# ambika-smr4x.net
KiCad netlist of a schematic drawn in EAGLE
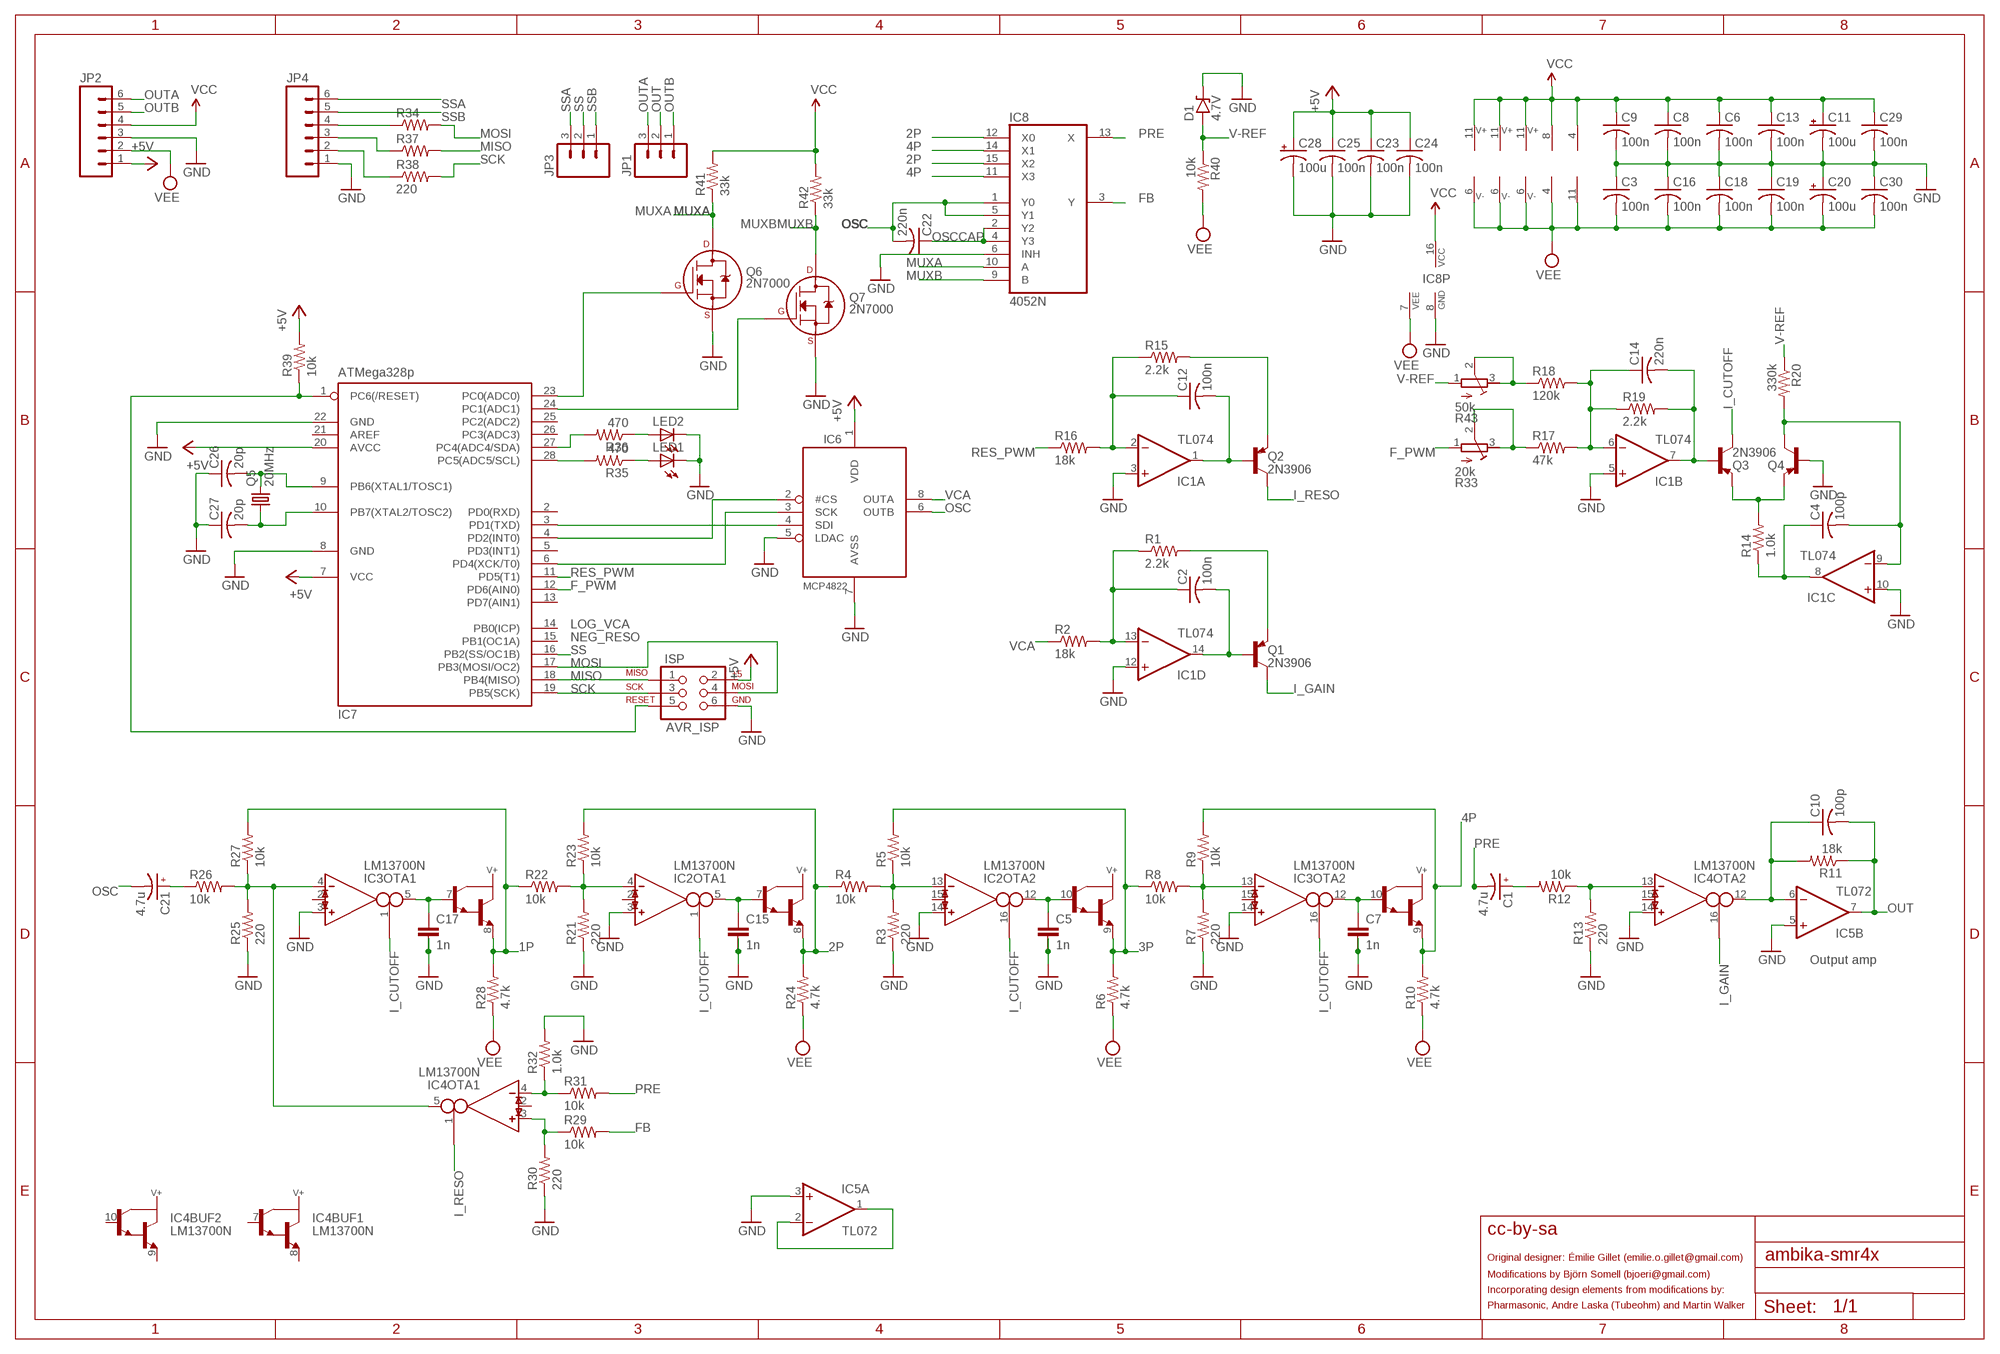
[diagram p0: schematic, sheet 1]

(export (version "E")
  (design (tool "Eeschema 10.0.6"))
  (components
    (comp (ref "C1")
      (value "4.7u")
      (footprint "eagle-import:E11-6.3")
      (libsource (lib "eagle-import") (part "CPOL-USE11-6.3"))
    )
    (comp (ref "C2")
      (value "100n")
      (footprint "eagle-import:C025-025X050")
      (libsource (lib "eagle-import") (part "C-US025-025X050"))
    )
    (comp (ref "C3")
      (value "100n")
      (footprint "eagle-import:C025-025X050")
      (libsource (lib "eagle-import") (part "C-US025-025X050"))
    )
    (comp (ref "C4")
      (value "100p")
      (footprint "eagle-import:C025-025X050")
      (libsource (lib "eagle-import") (part "C-US025-025X050"))
    )
    (comp (ref "C5")
      (value "1n")
      (footprint "eagle-import:C2.5_5-2")
      (libsource (lib "eagle-import") (part "C-2.5-5/2"))
    )
    (comp (ref "C6")
      (value "100n")
      (footprint "eagle-import:C025-025X050")
      (libsource (lib "eagle-import") (part "C-US025-025X050"))
    )
    (comp (ref "C7")
      (value "1n")
      (footprint "eagle-import:C2.5_5-2")
      (libsource (lib "eagle-import") (part "C-2.5-5/2"))
    )
    (comp (ref "C8")
      (value "100n")
      (footprint "eagle-import:C025-025X050")
      (libsource (lib "eagle-import") (part "C-US025-025X050"))
    )
    (comp (ref "C9")
      (value "100n")
      (footprint "eagle-import:C025-025X050")
      (libsource (lib "eagle-import") (part "C-US025-025X050"))
    )
    (comp (ref "C10")
      (value "100p")
      (footprint "eagle-import:C025-025X050")
      (libsource (lib "eagle-import") (part "C-US025-025X050"))
    )
    (comp (ref "C11")
      (value "100u")
      (footprint "eagle-import:E2,5-6")
      (libsource (lib "eagle-import") (part "CPOL-USE2.5-6"))
    )
    (comp (ref "C12")
      (value "100n")
      (footprint "eagle-import:C025-025X050")
      (libsource (lib "eagle-import") (part "C-US025-025X050"))
    )
    (comp (ref "C13")
      (value "100n")
      (footprint "eagle-import:C025-025X050")
      (libsource (lib "eagle-import") (part "C-US025-025X050"))
    )
    (comp (ref "C14")
      (value "220n")
      (footprint "eagle-import:C025-025X050")
      (libsource (lib "eagle-import") (part "C-US025-025X050"))
    )
    (comp (ref "C15")
      (value "1n")
      (footprint "eagle-import:C2.5_5-2")
      (libsource (lib "eagle-import") (part "C-2.5-5/2"))
    )
    (comp (ref "C16")
      (value "100n")
      (footprint "eagle-import:C025-025X050")
      (libsource (lib "eagle-import") (part "C-US025-025X050"))
    )
    (comp (ref "C17")
      (value "1n")
      (footprint "eagle-import:C2.5_5-2")
      (libsource (lib "eagle-import") (part "C-2.5-5/2"))
    )
    (comp (ref "C18")
      (value "100n")
      (footprint "eagle-import:C025-025X050")
      (libsource (lib "eagle-import") (part "C-US025-025X050"))
    )
    (comp (ref "C19")
      (value "100n")
      (footprint "eagle-import:C025-025X050")
      (libsource (lib "eagle-import") (part "C-US025-025X050"))
    )
    (comp (ref "C20")
      (value "100u")
      (footprint "eagle-import:E2,5-6")
      (libsource (lib "eagle-import") (part "CPOL-USE2.5-6"))
    )
    (comp (ref "C21")
      (value "4.7u")
      (footprint "eagle-import:E11-6.3")
      (libsource (lib "eagle-import") (part "CPOL-USE11-6.3"))
    )
    (comp (ref "C22")
      (value "220n")
      (footprint "eagle-import:C025-025X050")
      (libsource (lib "eagle-import") (part "C-US025-025X050"))
    )
    (comp (ref "C23")
      (value "100n")
      (footprint "eagle-import:C025-025X050")
      (libsource (lib "eagle-import") (part "C-US025-025X050"))
    )
    (comp (ref "C24")
      (value "100n")
      (footprint "eagle-import:C025-025X050")
      (libsource (lib "eagle-import") (part "C-US025-025X050"))
    )
    (comp (ref "C25")
      (value "100n")
      (footprint "eagle-import:C025-024X044")
      (libsource (lib "eagle-import") (part "C-US025-024X044"))
    )
    (comp (ref "C26")
      (value "20p")
      (footprint "eagle-import:C025-024X044")
      (libsource (lib "eagle-import") (part "C-US025-024X044"))
    )
    (comp (ref "C27")
      (value "20p")
      (footprint "eagle-import:C025-024X044")
      (libsource (lib "eagle-import") (part "C-US025-024X044"))
    )
    (comp (ref "C28")
      (value "100u")
      (footprint "eagle-import:E2,5-6")
      (libsource (lib "eagle-import") (part "CPOL-USE2.5-6"))
    )
    (comp (ref "C29")
      (value "100n")
      (footprint "eagle-import:C025-025X050")
      (libsource (lib "eagle-import") (part "C-US025-025X050"))
    )
    (comp (ref "C30")
      (value "100n")
      (footprint "eagle-import:C025-025X050")
      (libsource (lib "eagle-import") (part "C-US025-025X050"))
    )
    (comp (ref "D1")
      (value "4.7V")
      (footprint "eagle-import:D-5")
      (libsource (lib "eagle-import") (part "1N47XXDO35"))
    )
    (comp (ref "IC1")
      (value "TL074")
      (footprint "eagle-import:DIL14")
      (libsource (lib "eagle-import") (part "TL084P"))
    )
    (comp (ref "IC2")
      (value "LM13700N")
      (footprint "eagle-import:DIL16")
      (libsource (lib "eagle-import") (part "LM13700N"))
    )
    (comp (ref "IC3")
      (value "LM13700N")
      (footprint "eagle-import:DIL16")
      (libsource (lib "eagle-import") (part "LM13700N"))
    )
    (comp (ref "IC4")
      (value "LM13700N")
      (footprint "eagle-import:DIL16")
      (libsource (lib "eagle-import") (part "LM13700N"))
    )
    (comp (ref "IC5")
      (value "TL072")
      (footprint "eagle-import:DIL08")
      (libsource (lib "eagle-import") (part "TL072P"))
    )
    (comp (ref "IC6")
      (value "MCP4822")
      (footprint "eagle-import:DIL08")
      (libsource (lib "eagle-import") (part "MCP4822"))
    )
    (comp (ref "IC7")
      (value "ATMega328p")
      (footprint "eagle-import:DIL28-3")
      (libsource (lib "eagle-import") (part "MEGA8-P"))
    )
    (comp (ref "IC8")
      (value "4052N")
      (footprint "eagle-import:DIL16")
      (libsource (lib "eagle-import") (part "4052N"))
    )
    (comp (ref "ISP")
      (value "AVR_ISP")
      (footprint "eagle-import:2X3")
      (libsource (lib "eagle-import") (part "AVR_SPI_PRG_6PTH"))
    )
    (comp (ref "JP1")
      (value "M03PTH")
      (footprint "eagle-import:1X03")
      (libsource (lib "eagle-import") (part "M03PTH"))
    )
    (comp (ref "JP2")
      (value "M06SIP")
      (footprint "eagle-import:1X06")
      (libsource (lib "eagle-import") (part "M06SIP"))
    )
    (comp (ref "JP3")
      (value "M03PTH")
      (footprint "eagle-import:1X03")
      (libsource (lib "eagle-import") (part "M03PTH"))
    )
    (comp (ref "JP4")
      (value "M06SIP")
      (footprint "eagle-import:1X06")
      (libsource (lib "eagle-import") (part "M06SIP"))
    )
    (comp (ref "LED1")
      (value "LED3MM")
      (footprint "eagle-import:LED3MM")
      (libsource (lib "eagle-import") (part "LED3MM"))
    )
    (comp (ref "LED2")
      (value "LED3MM")
      (footprint "eagle-import:LED3MM")
      (libsource (lib "eagle-import") (part "LED3MM"))
    )
    (comp (ref "Q1")
      (value "2N3906")
      (footprint "eagle-import:TO92-")
      (libsource (lib "eagle-import") (part "2N3906-"))
    )
    (comp (ref "Q2")
      (value "2N3906")
      (footprint "eagle-import:TO92-")
      (libsource (lib "eagle-import") (part "2N3906-"))
    )
    (comp (ref "Q3")
      (value "2N3906")
      (footprint "eagle-import:TO92-")
      (libsource (lib "eagle-import") (part "2N3906-"))
    )
    (comp (ref "Q4")
      (value "2N3906")
      (footprint "eagle-import:TO92-")
      (libsource (lib "eagle-import") (part "2N3906-"))
    )
    (comp (ref "Q5")
      (value "20MHz")
      (footprint "eagle-import:HC49U-V")
      (libsource (lib "eagle-import") (part "CRYSTALHC49U-V"))
    )
    (comp (ref "Q6")
      (value "2N7000")
      (footprint "eagle-import:TO-92")
      (libsource (lib "eagle-import") (part "2N700_TO920"))
    )
    (comp (ref "Q7")
      (value "2N7000")
      (footprint "eagle-import:TO-92")
      (libsource (lib "eagle-import") (part "2N700_TO920"))
    )
    (comp (ref "R1")
      (value "2.2k")
      (footprint "eagle-import:0204_7")
      (libsource (lib "eagle-import") (part "R-US_0204/7"))
    )
    (comp (ref "R2")
      (value "18k")
      (footprint "eagle-import:0204_7")
      (libsource (lib "eagle-import") (part "R-US_0204/7"))
    )
    (comp (ref "R3")
      (value "220")
      (footprint "eagle-import:0204_7")
      (libsource (lib "eagle-import") (part "R-US_0204/7"))
    )
    (comp (ref "R4")
      (value "10k")
      (footprint "eagle-import:0204_7")
      (libsource (lib "eagle-import") (part "R-US_0204/7"))
    )
    (comp (ref "R5")
      (value "10k")
      (footprint "eagle-import:0204_7")
      (libsource (lib "eagle-import") (part "R-US_0204/7"))
    )
    (comp (ref "R6")
      (value "4.7k")
      (footprint "eagle-import:0204_7")
      (libsource (lib "eagle-import") (part "R-US_0204/7"))
    )
    (comp (ref "R7")
      (value "220")
      (footprint "eagle-import:0204_7")
      (libsource (lib "eagle-import") (part "R-US_0204/7"))
    )
    (comp (ref "R8")
      (value "10k")
      (footprint "eagle-import:0204_7")
      (libsource (lib "eagle-import") (part "R-US_0204/7"))
    )
    (comp (ref "R9")
      (value "10k")
      (footprint "eagle-import:0204_7")
      (libsource (lib "eagle-import") (part "R-US_0204/7"))
    )
    (comp (ref "R10")
      (value "4.7k")
      (footprint "eagle-import:0204_7")
      (libsource (lib "eagle-import") (part "R-US_0204/7"))
    )
    (comp (ref "R11")
      (value "18k")
      (footprint "eagle-import:0204_7")
      (libsource (lib "eagle-import") (part "R-US_0204/7"))
    )
    (comp (ref "R12")
      (value "10k")
      (footprint "eagle-import:0204_7")
      (libsource (lib "eagle-import") (part "R-US_0204/7"))
    )
    (comp (ref "R13")
      (value "220")
      (footprint "eagle-import:0204_7")
      (libsource (lib "eagle-import") (part "R-US_0204/7"))
    )
    (comp (ref "R14")
      (value "1.0k")
      (footprint "eagle-import:0204_7")
      (libsource (lib "eagle-import") (part "R-US_0204/7"))
    )
    (comp (ref "R15")
      (value "2.2k")
      (footprint "eagle-import:0204_7")
      (libsource (lib "eagle-import") (part "R-US_0204/7"))
    )
    (comp (ref "R16")
      (value "18k")
      (footprint "eagle-import:0204_7")
      (libsource (lib "eagle-import") (part "R-US_0204/7"))
    )
    (comp (ref "R17")
      (value "47k")
      (footprint "eagle-import:0204_7")
      (libsource (lib "eagle-import") (part "R-US_0204/7"))
    )
    (comp (ref "R18")
      (value "120k")
      (footprint "eagle-import:0204_7")
      (libsource (lib "eagle-import") (part "R-US_0204/7"))
    )
    (comp (ref "R19")
      (value "2.2k")
      (footprint "eagle-import:0204_7")
      (libsource (lib "eagle-import") (part "R-US_0204/7"))
    )
    (comp (ref "R20")
      (value "330k")
      (footprint "eagle-import:0204_7")
      (libsource (lib "eagle-import") (part "R-US_0204/7"))
    )
    (comp (ref "R21")
      (value "220")
      (footprint "eagle-import:0204_7")
      (libsource (lib "eagle-import") (part "R-US_0204/7"))
    )
    (comp (ref "R22")
      (value "10k")
      (footprint "eagle-import:0204_7")
      (libsource (lib "eagle-import") (part "R-US_0204/7"))
    )
    (comp (ref "R23")
      (value "10k")
      (footprint "eagle-import:0204_7")
      (libsource (lib "eagle-import") (part "R-US_0204/7"))
    )
    (comp (ref "R24")
      (value "4.7k")
      (footprint "eagle-import:0204_7")
      (libsource (lib "eagle-import") (part "R-US_0204/7"))
    )
    (comp (ref "R25")
      (value "220")
      (footprint "eagle-import:0204_7")
      (libsource (lib "eagle-import") (part "R-US_0204/7"))
    )
    (comp (ref "R26")
      (value "10k")
      (footprint "eagle-import:0204_7")
      (libsource (lib "eagle-import") (part "R-US_0204/7"))
    )
    (comp (ref "R27")
      (value "10k")
      (footprint "eagle-import:0204_7")
      (libsource (lib "eagle-import") (part "R-US_0204/7"))
    )
    (comp (ref "R28")
      (value "4.7k")
      (footprint "eagle-import:0204_7")
      (libsource (lib "eagle-import") (part "R-US_0204/7"))
    )
    (comp (ref "R29")
      (value "10k")
      (footprint "eagle-import:0204_7")
      (libsource (lib "eagle-import") (part "R-US_0204/7"))
    )
    (comp (ref "R30")
      (value "220")
      (footprint "eagle-import:0204_7")
      (libsource (lib "eagle-import") (part "R-US_0204/7"))
    )
    (comp (ref "R31")
      (value "10k")
      (footprint "eagle-import:0204_7")
      (libsource (lib "eagle-import") (part "R-US_0204/7"))
    )
    (comp (ref "R32")
      (value "1.0k")
      (footprint "eagle-import:0204_7")
      (libsource (lib "eagle-import") (part "R-US_0204/7"))
    )
    (comp (ref "R33")
      (value "20k")
      (footprint "eagle-import:RTRIM3296P")
      (libsource (lib "eagle-import") (part "R-TRIMM3296P"))
    )
    (comp (ref "R34")
      (value "220")
      (footprint "eagle-import:0204_7")
      (libsource (lib "eagle-import") (part "R-US_0204/7"))
    )
    (comp (ref "R35")
      (value "470")
      (footprint "eagle-import:0204_7")
      (libsource (lib "eagle-import") (part "R-US_0204/7"))
    )
    (comp (ref "R36")
      (value "470")
      (footprint "eagle-import:0204_7")
      (libsource (lib "eagle-import") (part "R-US_0204/7"))
    )
    (comp (ref "R37")
      (value "220")
      (footprint "eagle-import:0204_7")
      (libsource (lib "eagle-import") (part "R-US_0204/7"))
    )
    (comp (ref "R38")
      (value "220")
      (footprint "eagle-import:0204_7")
      (libsource (lib "eagle-import") (part "R-US_0204/7"))
    )
    (comp (ref "R39")
      (value "10k")
      (footprint "eagle-import:0204_7")
      (libsource (lib "eagle-import") (part "R-US_0204/7"))
    )
    (comp (ref "R40")
      (value "10k")
      (footprint "eagle-import:0204_7")
      (libsource (lib "eagle-import") (part "R-US_0204/7"))
    )
    (comp (ref "R41")
      (value "33k")
      (footprint "eagle-import:0204_7")
      (libsource (lib "eagle-import") (part "R-US_0204/7"))
    )
    (comp (ref "R42")
      (value "33k")
      (footprint "eagle-import:0204_7")
      (libsource (lib "eagle-import") (part "R-US_0204/7"))
    )
    (comp (ref "R43")
      (value "50k")
      (footprint "eagle-import:RTRIM3296P")
      (libsource (lib "eagle-import") (part "R-TRIMM3296P"))
    )
  )
  (nets
    (net (code "1") (name "+5V") (class "Default")
      (node (ref "C23") (pin "1") (pinfunction "1_1") (pintype "passive"))
      (node (ref "C24") (pin "1") (pinfunction "1_1") (pintype "passive"))
      (node (ref "C25") (pin "1") (pinfunction "1_1") (pintype "passive"))
      (node (ref "C28") (pin "+") (pinfunction "+_+") (pintype "passive"))
      (node (ref "IC6") (pin "1") (pinfunction "VDD_1") (pintype "power_in"))
      (node (ref "IC7") (pin "20") (pinfunction "AVCC_20") (pintype "power_in"))
      (node (ref "IC7") (pin "7") (pinfunction "VCC_7") (pintype "power_in"))
      (node (ref "ISP") (pin "2") (pinfunction "2_2") (pintype "passive"))
      (node (ref "JP2") (pin "1") (pinfunction "1_1") (pintype "passive"))
      (node (ref "R39") (pin "2") (pinfunction "2_2") (pintype "passive"))
    )
    (net (code "2") (name "/1P") (class "Default")
      (node (ref "IC3") (pin "8") (pinfunction "E_8") (pintype "passive"))
      (node (ref "R22") (pin "1") (pinfunction "1_1") (pintype "passive"))
      (node (ref "R27") (pin "2") (pinfunction "2_2") (pintype "passive"))
      (node (ref "R28") (pin "2") (pinfunction "2_2") (pintype "passive"))
    )
    (net (code "3") (name "/2P") (class "Default")
      (node (ref "IC2") (pin "8") (pinfunction "E_8") (pintype "passive"))
      (node (ref "IC8") (pin "12") (pinfunction "X0_12") (pintype "bidirectional"))
      (node (ref "IC8") (pin "15") (pinfunction "X2_15") (pintype "bidirectional"))
      (node (ref "R23") (pin "2") (pinfunction "2_2") (pintype "passive"))
      (node (ref "R24") (pin "2") (pinfunction "2_2") (pintype "passive"))
      (node (ref "R4") (pin "1") (pinfunction "1_1") (pintype "passive"))
    )
    (net (code "4") (name "/3P") (class "Default")
      (node (ref "IC2") (pin "9") (pinfunction "E_9") (pintype "passive"))
      (node (ref "R5") (pin "2") (pinfunction "2_2") (pintype "passive"))
      (node (ref "R6") (pin "2") (pinfunction "2_2") (pintype "passive"))
      (node (ref "R8") (pin "1") (pinfunction "1_1") (pintype "passive"))
    )
    (net (code "5") (name "/4P") (class "Default")
      (node (ref "IC3") (pin "9") (pinfunction "E_9") (pintype "passive"))
      (node (ref "IC8") (pin "11") (pinfunction "X3_11") (pintype "bidirectional"))
      (node (ref "IC8") (pin "14") (pinfunction "X1_14") (pintype "bidirectional"))
      (node (ref "R10") (pin "2") (pinfunction "2_2") (pintype "passive"))
      (node (ref "R9") (pin "2") (pinfunction "2_2") (pintype "passive"))
    )
    (net (code "6") (name "/FB") (class "Default")
      (node (ref "IC8") (pin "3") (pinfunction "Y_3") (pintype "bidirectional"))
      (node (ref "R29") (pin "2") (pinfunction "2_2") (pintype "passive"))
    )
    (net (code "7") (name "/F_PWM") (class "Default")
      (node (ref "IC7") (pin "12") (pinfunction "PD6(AIN0)_12") (pintype "bidirectional"))
      (node (ref "R33") (pin "1") (pinfunction "E_1") (pintype "passive"))
    )
    (net (code "8") (name "/I_CUTOFF") (class "Default")
      (node (ref "IC2") (pin "1") (pinfunction "I_BIAS_1") (pintype "input"))
      (node (ref "IC2") (pin "16") (pinfunction "I_BIAS_16") (pintype "input"))
      (node (ref "IC3") (pin "1") (pinfunction "I_BIAS_1") (pintype "input"))
      (node (ref "IC3") (pin "16") (pinfunction "I_BIAS_16") (pintype "input"))
      (node (ref "Q3") (pin "1") (pinfunction "C_1") (pintype "passive"))
    )
    (net (code "9") (name "/I_GAIN") (class "Default")
      (node (ref "IC4") (pin "16") (pinfunction "I_BIAS_16") (pintype "input"))
      (node (ref "Q1") (pin "1") (pinfunction "C_1") (pintype "passive"))
    )
    (net (code "10") (name "/I_RESO") (class "Default")
      (node (ref "IC4") (pin "1") (pinfunction "I_BIAS_1") (pintype "input"))
      (node (ref "Q2") (pin "1") (pinfunction "C_1") (pintype "passive"))
    )
    (net (code "11") (name "/MISO") (class "Default")
      (node (ref "IC7") (pin "18") (pinfunction "PB4(MISO)_18") (pintype "bidirectional"))
      (node (ref "ISP") (pin "1") (pinfunction "1_1") (pintype "passive"))
      (node (ref "R37") (pin "2") (pinfunction "2_2") (pintype "passive"))
    )
    (net (code "12") (name "/MOSI") (class "Default")
      (node (ref "IC7") (pin "17") (pinfunction "PB3(MOSI/OC2)_17") (pintype "bidirectional"))
      (node (ref "ISP") (pin "4") (pinfunction "4_4") (pintype "passive"))
      (node (ref "R34") (pin "2") (pinfunction "2_2") (pintype "passive"))
    )
    (net (code "13") (name "/MUXA") (class "Default")
      (node (ref "IC8") (pin "10") (pinfunction "A_10") (pintype "input"))
      (node (ref "Q6") (pin "3") (pinfunction "D_3") (pintype "bidirectional"))
      (node (ref "R41") (pin "1") (pinfunction "1_1") (pintype "passive"))
    )
    (net (code "14") (name "/MUXB") (class "Default")
      (node (ref "IC8") (pin "9") (pinfunction "B_9") (pintype "input"))
      (node (ref "Q7") (pin "3") (pinfunction "D_3") (pintype "bidirectional"))
      (node (ref "R42") (pin "1") (pinfunction "1_1") (pintype "passive"))
    )
    (net (code "15") (name "/OSC") (class "Default")
      (node (ref "C21") (pin "-") (pinfunction "2_-") (pintype "passive"))
      (node (ref "C22") (pin "2") (pinfunction "2_2") (pintype "passive"))
      (node (ref "IC6") (pin "6") (pinfunction "OUTB_6") (pintype "output"))
      (node (ref "IC8") (pin "1") (pinfunction "Y0_1") (pintype "bidirectional"))
      (node (ref "IC8") (pin "5") (pinfunction "Y1_5") (pintype "bidirectional"))
    )
    (net (code "16") (name "/OSCCAP") (class "Default")
      (node (ref "C22") (pin "1") (pinfunction "1_1") (pintype "passive"))
      (node (ref "IC8") (pin "2") (pinfunction "Y2_2") (pintype "bidirectional"))
      (node (ref "IC8") (pin "4") (pinfunction "Y3_4") (pintype "bidirectional"))
    )
    (net (code "17") (name "/OUT") (class "Default")
      (node (ref "C10") (pin "2") (pinfunction "2_2") (pintype "passive"))
      (node (ref "IC5") (pin "7") (pinfunction "OUT_7") (pintype "output"))
      (node (ref "JP1") (pin "2") (pinfunction "2_2") (pintype "passive"))
      (node (ref "R11") (pin "1") (pinfunction "1_1") (pintype "passive"))
    )
    (net (code "18") (name "/OUTA") (class "Default")
      (node (ref "JP1") (pin "3") (pinfunction "3_3") (pintype "passive"))
      (node (ref "JP2") (pin "6") (pinfunction "6_6") (pintype "passive"))
    )
    (net (code "19") (name "/OUTB") (class "Default")
      (node (ref "JP1") (pin "1") (pinfunction "1_1") (pintype "passive"))
      (node (ref "JP2") (pin "5") (pinfunction "5_5") (pintype "passive"))
    )
    (net (code "20") (name "/PRE") (class "Default")
      (node (ref "C1") (pin "-") (pinfunction "2_-") (pintype "passive"))
      (node (ref "IC8") (pin "13") (pinfunction "X_13") (pintype "bidirectional"))
      (node (ref "R31") (pin "2") (pinfunction "2_2") (pintype "passive"))
    )
    (net (code "21") (name "/RES_PWM") (class "Default")
      (node (ref "IC7") (pin "11") (pinfunction "PD5(T1)_11") (pintype "bidirectional"))
      (node (ref "R16") (pin "1") (pinfunction "1_1") (pintype "passive"))
    )
    (net (code "22") (name "/SCK") (class "Default")
      (node (ref "IC7") (pin "19") (pinfunction "PB5(SCK)_19") (pintype "bidirectional"))
      (node (ref "ISP") (pin "3") (pinfunction "3_3") (pintype "passive"))
      (node (ref "R38") (pin "2") (pinfunction "2_2") (pintype "passive"))
    )
    (net (code "23") (name "/SS") (class "Default")
      (node (ref "IC7") (pin "16") (pinfunction "PB2(SS/OC1B)_16") (pintype "bidirectional"))
      (node (ref "JP3") (pin "2") (pinfunction "2_2") (pintype "passive"))
    )
    (net (code "24") (name "/SSA") (class "Default")
      (node (ref "JP3") (pin "3") (pinfunction "3_3") (pintype "passive"))
      (node (ref "JP4") (pin "6") (pinfunction "6_6") (pintype "passive"))
    )
    (net (code "25") (name "/SSB") (class "Default")
      (node (ref "JP3") (pin "1") (pinfunction "1_1") (pintype "passive"))
      (node (ref "JP4") (pin "5") (pinfunction "5_5") (pintype "passive"))
    )
    (net (code "26") (name "/V-REF") (class "Default")
      (node (ref "D1") (pin "A") (pinfunction "A_A") (pintype "passive"))
      (node (ref "R20") (pin "1") (pinfunction "1_1") (pintype "passive"))
      (node (ref "R40") (pin "1") (pinfunction "1_1") (pintype "passive"))
      (node (ref "R43") (pin "1") (pinfunction "E_1") (pintype "passive"))
    )
    (net (code "27") (name "/VCA") (class "Default")
      (node (ref "IC6") (pin "8") (pinfunction "OUTA_8") (pintype "output"))
      (node (ref "R2") (pin "1") (pinfunction "1_1") (pintype "passive"))
    )
    (net (code "28") (name "GND") (class "Default")
      (node (ref "C11") (pin "-") (pinfunction "-_-") (pintype "passive"))
      (node (ref "C13") (pin "2") (pinfunction "2_2") (pintype "passive"))
      (node (ref "C15") (pin "2") (pinfunction "2_2") (pintype "passive"))
      (node (ref "C15") (pin "3") (pinfunction "3_3") (pintype "passive"))
      (node (ref "C16") (pin "1") (pinfunction "1_1") (pintype "passive"))
      (node (ref "C17") (pin "2") (pinfunction "2_2") (pintype "passive"))
      (node (ref "C17") (pin "3") (pinfunction "3_3") (pintype "passive"))
      (node (ref "C18") (pin "1") (pinfunction "1_1") (pintype "passive"))
      (node (ref "C19") (pin "1") (pinfunction "1_1") (pintype "passive"))
      (node (ref "C20") (pin "+") (pinfunction "+_+") (pintype "passive"))
      (node (ref "C23") (pin "2") (pinfunction "2_2") (pintype "passive"))
      (node (ref "C24") (pin "2") (pinfunction "2_2") (pintype "passive"))
      (node (ref "C25") (pin "2") (pinfunction "2_2") (pintype "passive"))
      (node (ref "C26") (pin "1") (pinfunction "1_1") (pintype "passive"))
      (node (ref "C27") (pin "1") (pinfunction "1_1") (pintype "passive"))
      (node (ref "C28") (pin "-") (pinfunction "-_-") (pintype "passive"))
      (node (ref "C29") (pin "2") (pinfunction "2_2") (pintype "passive"))
      (node (ref "C3") (pin "1") (pinfunction "1_1") (pintype "passive"))
      (node (ref "C30") (pin "1") (pinfunction "1_1") (pintype "passive"))
      (node (ref "C5") (pin "2") (pinfunction "2_2") (pintype "passive"))
      (node (ref "C5") (pin "3") (pinfunction "3_3") (pintype "passive"))
      (node (ref "C6") (pin "2") (pinfunction "2_2") (pintype "passive"))
      (node (ref "C7") (pin "2") (pinfunction "2_2") (pintype "passive"))
      (node (ref "C7") (pin "3") (pinfunction "3_3") (pintype "passive"))
      (node (ref "C8") (pin "2") (pinfunction "2_2") (pintype "passive"))
      (node (ref "C9") (pin "2") (pinfunction "2_2") (pintype "passive"))
      (node (ref "D1") (pin "C") (pinfunction "C_C") (pintype "passive"))
      (node (ref "IC1") (pin "10") (pinfunction "+IN_10") (pintype "input"))
      (node (ref "IC1") (pin "12") (pinfunction "+IN_12") (pintype "input"))
      (node (ref "IC1") (pin "3") (pinfunction "+IN_3") (pintype "input"))
      (node (ref "IC1") (pin "5") (pinfunction "+IN_5") (pintype "input"))
      (node (ref "IC2") (pin "14") (pinfunction "IN_P_14") (pintype "input"))
      (node (ref "IC2") (pin "3") (pinfunction "IN_P_3") (pintype "input"))
      (node (ref "IC3") (pin "14") (pinfunction "IN_P_14") (pintype "input"))
      (node (ref "IC3") (pin "3") (pinfunction "IN_P_3") (pintype "input"))
      (node (ref "IC4") (pin "14") (pinfunction "IN_P_14") (pintype "input"))
      (node (ref "IC5") (pin "3") (pinfunction "+IN_3") (pintype "input"))
      (node (ref "IC5") (pin "5") (pinfunction "+IN_5") (pintype "input"))
      (node (ref "IC6") (pin "5") (pinfunction "LDAC_5") (pintype "input"))
      (node (ref "IC6") (pin "7") (pinfunction "AVSS_7") (pintype "power_in"))
      (node (ref "IC7") (pin "22") (pinfunction "GND_22") (pintype "power_in"))
      (node (ref "IC7") (pin "8") (pinfunction "GND_8") (pintype "power_in"))
      (node (ref "IC8") (pin "6") (pinfunction "INH_6") (pintype "input"))
      (node (ref "IC8") (pin "8") (pinfunction "GND_8") (pintype "power_in"))
      (node (ref "ISP") (pin "6") (pinfunction "6_6") (pintype "passive"))
      (node (ref "JP2") (pin "3") (pinfunction "3_3") (pintype "passive"))
      (node (ref "JP4") (pin "1") (pinfunction "1_1") (pintype "passive"))
      (node (ref "LED1") (pin "K") (pinfunction "C_K") (pintype "passive"))
      (node (ref "LED2") (pin "K") (pinfunction "C_K") (pintype "passive"))
      (node (ref "Q4") (pin "2") (pinfunction "B_2") (pintype "passive"))
      (node (ref "Q6") (pin "1") (pinfunction "S_1") (pintype "bidirectional"))
      (node (ref "Q7") (pin "1") (pinfunction "S_1") (pintype "bidirectional"))
      (node (ref "R13") (pin "1") (pinfunction "1_1") (pintype "passive"))
      (node (ref "R21") (pin "1") (pinfunction "1_1") (pintype "passive"))
      (node (ref "R25") (pin "1") (pinfunction "1_1") (pintype "passive"))
      (node (ref "R3") (pin "1") (pinfunction "1_1") (pintype "passive"))
      (node (ref "R30") (pin "1") (pinfunction "1_1") (pintype "passive"))
      (node (ref "R32") (pin "2") (pinfunction "2_2") (pintype "passive"))
      (node (ref "R7") (pin "1") (pinfunction "1_1") (pintype "passive"))
    )
    (net (code "29") (name "Net-(C1-1)") (class "Default")
      (node (ref "C1") (pin "+") (pinfunction "1_+") (pintype "passive"))
      (node (ref "R12") (pin "2") (pinfunction "2_2") (pintype "passive"))
    )
    (net (code "30") (name "Net-(C21-1)") (class "Default")
      (node (ref "C21") (pin "+") (pinfunction "1_+") (pintype "passive"))
      (node (ref "R26") (pin "1") (pinfunction "1_1") (pintype "passive"))
    )
    (net (code "31") (name "Net-(IC1A--IN)") (class "Default")
      (node (ref "C12") (pin "1") (pinfunction "1_1") (pintype "passive"))
      (node (ref "IC1") (pin "2") (pinfunction "-IN_2") (pintype "input"))
      (node (ref "R15") (pin "1") (pinfunction "1_1") (pintype "passive"))
      (node (ref "R16") (pin "2") (pinfunction "2_2") (pintype "passive"))
    )
    (net (code "32") (name "Net-(IC1A-OUT)") (class "Default")
      (node (ref "C12") (pin "2") (pinfunction "2_2") (pintype "passive"))
      (node (ref "IC1") (pin "1") (pinfunction "OUT_1") (pintype "output"))
      (node (ref "Q2") (pin "2") (pinfunction "B_2") (pintype "passive"))
    )
    (net (code "33") (name "Net-(IC1B--IN)") (class "Default")
      (node (ref "C14") (pin "1") (pinfunction "1_1") (pintype "passive"))
      (node (ref "IC1") (pin "6") (pinfunction "-IN_6") (pintype "input"))
      (node (ref "R17") (pin "2") (pinfunction "2_2") (pintype "passive"))
      (node (ref "R18") (pin "2") (pinfunction "2_2") (pintype "passive"))
      (node (ref "R19") (pin "1") (pinfunction "1_1") (pintype "passive"))
    )
    (net (code "34") (name "Net-(IC1B-OUT)") (class "Default")
      (node (ref "C14") (pin "2") (pinfunction "2_2") (pintype "passive"))
      (node (ref "IC1") (pin "7") (pinfunction "OUT_7") (pintype "output"))
      (node (ref "Q3") (pin "2") (pinfunction "B_2") (pintype "passive"))
      (node (ref "R19") (pin "2") (pinfunction "2_2") (pintype "passive"))
    )
    (net (code "35") (name "Net-(IC1C--IN)") (class "Default")
      (node (ref "C4") (pin "2") (pinfunction "2_2") (pintype "passive"))
      (node (ref "IC1") (pin "9") (pinfunction "-IN_9") (pintype "input"))
      (node (ref "Q4") (pin "1") (pinfunction "C_1") (pintype "passive"))
      (node (ref "R20") (pin "2") (pinfunction "2_2") (pintype "passive"))
    )
    (net (code "36") (name "Net-(IC1C-OUT)") (class "Default")
      (node (ref "C4") (pin "1") (pinfunction "1_1") (pintype "passive"))
      (node (ref "IC1") (pin "8") (pinfunction "OUT_8") (pintype "output"))
      (node (ref "R14") (pin "1") (pinfunction "1_1") (pintype "passive"))
    )
    (net (code "37") (name "Net-(IC1D--IN)") (class "Default")
      (node (ref "C2") (pin "1") (pinfunction "1_1") (pintype "passive"))
      (node (ref "IC1") (pin "13") (pinfunction "-IN_13") (pintype "input"))
      (node (ref "R1") (pin "1") (pinfunction "1_1") (pintype "passive"))
      (node (ref "R2") (pin "2") (pinfunction "2_2") (pintype "passive"))
    )
    (net (code "38") (name "Net-(IC1D-OUT)") (class "Default")
      (node (ref "C2") (pin "2") (pinfunction "2_2") (pintype "passive"))
      (node (ref "IC1") (pin "14") (pinfunction "OUT_14") (pintype "output"))
      (node (ref "Q1") (pin "2") (pinfunction "B_2") (pintype "passive"))
    )
    (net (code "39") (name "Net-(IC2A-B)") (class "Default")
      (node (ref "C15") (pin "1") (pinfunction "1_1") (pintype "passive"))
      (node (ref "IC2") (pin "5") (pinfunction "OUT_5") (pintype "output"))
      (node (ref "IC2") (pin "7") (pinfunction "B_7") (pintype "passive"))
    )
    (net (code "40") (name "Net-(IC2B-B)") (class "Default")
      (node (ref "C5") (pin "1") (pinfunction "1_1") (pintype "passive"))
      (node (ref "IC2") (pin "10") (pinfunction "B_10") (pintype "passive"))
      (node (ref "IC2") (pin "12") (pinfunction "OUT_12") (pintype "output"))
    )
    (net (code "41") (name "Net-(IC2C-IN_N)") (class "Default")
      (node (ref "IC2") (pin "4") (pinfunction "IN_N_4") (pintype "input"))
      (node (ref "R21") (pin "2") (pinfunction "2_2") (pintype "passive"))
      (node (ref "R22") (pin "2") (pinfunction "2_2") (pintype "passive"))
      (node (ref "R23") (pin "1") (pinfunction "1_1") (pintype "passive"))
    )
    (net (code "42") (name "Net-(IC2D-IN_N)") (class "Default")
      (node (ref "IC2") (pin "13") (pinfunction "IN_N_13") (pintype "input"))
      (node (ref "R3") (pin "2") (pinfunction "2_2") (pintype "passive"))
      (node (ref "R4") (pin "2") (pinfunction "2_2") (pintype "passive"))
      (node (ref "R5") (pin "1") (pinfunction "1_1") (pintype "passive"))
    )
    (net (code "43") (name "Net-(IC3A-B)") (class "Default")
      (node (ref "C17") (pin "1") (pinfunction "1_1") (pintype "passive"))
      (node (ref "IC3") (pin "5") (pinfunction "OUT_5") (pintype "output"))
      (node (ref "IC3") (pin "7") (pinfunction "B_7") (pintype "passive"))
    )
    (net (code "44") (name "Net-(IC3B-B)") (class "Default")
      (node (ref "C7") (pin "1") (pinfunction "1_1") (pintype "passive"))
      (node (ref "IC3") (pin "10") (pinfunction "B_10") (pintype "passive"))
      (node (ref "IC3") (pin "12") (pinfunction "OUT_12") (pintype "output"))
    )
    (net (code "45") (name "Net-(IC3C-IN_N)") (class "Default")
      (node (ref "IC3") (pin "4") (pinfunction "IN_N_4") (pintype "input"))
      (node (ref "IC4") (pin "5") (pinfunction "OUT_5") (pintype "output"))
      (node (ref "R25") (pin "2") (pinfunction "2_2") (pintype "passive"))
      (node (ref "R26") (pin "2") (pinfunction "2_2") (pintype "passive"))
      (node (ref "R27") (pin "1") (pinfunction "1_1") (pintype "passive"))
    )
    (net (code "46") (name "Net-(IC3D-IN_N)") (class "Default")
      (node (ref "IC3") (pin "13") (pinfunction "IN_N_13") (pintype "input"))
      (node (ref "R7") (pin "2") (pinfunction "2_2") (pintype "passive"))
      (node (ref "R8") (pin "2") (pinfunction "2_2") (pintype "passive"))
      (node (ref "R9") (pin "1") (pinfunction "1_1") (pintype "passive"))
    )
    (net (code "47") (name "Net-(IC4C-IN_N)") (class "Default")
      (node (ref "IC4") (pin "4") (pinfunction "IN_N_4") (pintype "input"))
      (node (ref "R31") (pin "1") (pinfunction "1_1") (pintype "passive"))
      (node (ref "R32") (pin "1") (pinfunction "1_1") (pintype "passive"))
    )
    (net (code "48") (name "Net-(IC4C-IN_P)") (class "Default")
      (node (ref "IC4") (pin "3") (pinfunction "IN_P_3") (pintype "input"))
      (node (ref "R29") (pin "1") (pinfunction "1_1") (pintype "passive"))
      (node (ref "R30") (pin "2") (pinfunction "2_2") (pintype "passive"))
    )
    (net (code "49") (name "Net-(IC4D-IN_N)") (class "Default")
      (node (ref "IC4") (pin "13") (pinfunction "IN_N_13") (pintype "input"))
      (node (ref "R12") (pin "1") (pinfunction "1_1") (pintype "passive"))
      (node (ref "R13") (pin "2") (pinfunction "2_2") (pintype "passive"))
    )
    (net (code "50") (name "Net-(IC4D-OUT)") (class "Default")
      (node (ref "C10") (pin "1") (pinfunction "1_1") (pintype "passive"))
      (node (ref "IC4") (pin "12") (pinfunction "OUT_12") (pintype "output"))
      (node (ref "IC5") (pin "6") (pinfunction "-IN_6") (pintype "input"))
      (node (ref "R11") (pin "2") (pinfunction "2_2") (pintype "passive"))
    )
    (net (code "51") (name "Net-(IC5A--IN)") (class "Default")
      (node (ref "IC5") (pin "1") (pinfunction "OUT_1") (pintype "output"))
      (node (ref "IC5") (pin "2") (pinfunction "-IN_2") (pintype "input"))
    )
    (net (code "52") (name "Net-(IC6-#CS)") (class "Default")
      (node (ref "IC6") (pin "2") (pinfunction "#CS_2") (pintype "input"))
      (node (ref "IC7") (pin "4") (pinfunction "PD2(INT0)_4") (pintype "bidirectional"))
    )
    (net (code "53") (name "Net-(IC6-SCK)") (class "Default")
      (node (ref "IC6") (pin "3") (pinfunction "SCK_3") (pintype "input"))
      (node (ref "IC7") (pin "6") (pinfunction "PD4(XCK/T0)_6") (pintype "bidirectional"))
    )
    (net (code "54") (name "Net-(IC6-SDI)") (class "Default")
      (node (ref "IC6") (pin "4") (pinfunction "SDI_4") (pintype "input"))
      (node (ref "IC7") (pin "3") (pinfunction "PD1(TXD)_3") (pintype "bidirectional"))
    )
    (net (code "55") (name "Net-(IC7-PB6(XTAL1{slash}TOSC1))") (class "Default")
      (node (ref "C26") (pin "2") (pinfunction "2_2") (pintype "passive"))
      (node (ref "IC7") (pin "9") (pinfunction "PB6(XTAL1/TOSC1)_9") (pintype "bidirectional"))
      (node (ref "Q5") (pin "2") (pinfunction "2_2") (pintype "passive"))
    )
    (net (code "56") (name "Net-(IC7-PB7(XTAL2{slash}TOSC2))") (class "Default")
      (node (ref "C27") (pin "2") (pinfunction "2_2") (pintype "passive"))
      (node (ref "IC7") (pin "10") (pinfunction "PB7(XTAL2/TOSC2)_10") (pintype "bidirectional"))
      (node (ref "Q5") (pin "1") (pinfunction "1_1") (pintype "passive"))
    )
    (net (code "57") (name "Net-(IC7-PC0(ADC0))") (class "Default")
      (node (ref "IC7") (pin "23") (pinfunction "PC0(ADC0)_23") (pintype "bidirectional"))
      (node (ref "Q6") (pin "2") (pinfunction "G_2") (pintype "tri_state"))
    )
    (net (code "58") (name "Net-(IC7-PC1(ADC1))") (class "Default")
      (node (ref "IC7") (pin "24") (pinfunction "PC1(ADC1)_24") (pintype "bidirectional"))
      (node (ref "Q7") (pin "2") (pinfunction "G_2") (pintype "tri_state"))
    )
    (net (code "59") (name "Net-(IC7-PC4(ADC4{slash}SDA))") (class "Default")
      (node (ref "IC7") (pin "27") (pinfunction "PC4(ADC4/SDA)_27") (pintype "bidirectional"))
      (node (ref "R36") (pin "2") (pinfunction "2_2") (pintype "passive"))
    )
    (net (code "60") (name "Net-(IC7-PC5(ADC5{slash}SCL))") (class "Default")
      (node (ref "IC7") (pin "28") (pinfunction "PC5(ADC5/SCL)_28") (pintype "bidirectional"))
      (node (ref "R35") (pin "2") (pinfunction "2_2") (pintype "passive"))
    )
    (net (code "61") (name "Net-(IC7-PC6({slash}RESET))") (class "Default")
      (node (ref "IC7") (pin "1") (pinfunction "PC6(/RESET)_1") (pintype "bidirectional"))
      (node (ref "ISP") (pin "5") (pinfunction "5_5") (pintype "passive"))
      (node (ref "R39") (pin "1") (pinfunction "1_1") (pintype "passive"))
    )
    (net (code "62") (name "Net-(JP4-Pad2)") (class "Default")
      (node (ref "JP4") (pin "2") (pinfunction "2_2") (pintype "passive"))
      (node (ref "R38") (pin "1") (pinfunction "1_1") (pintype "passive"))
    )
    (net (code "63") (name "Net-(JP4-Pad3)") (class "Default")
      (node (ref "JP4") (pin "3") (pinfunction "3_3") (pintype "passive"))
      (node (ref "R37") (pin "1") (pinfunction "1_1") (pintype "passive"))
    )
    (net (code "64") (name "Net-(JP4-Pad4)") (class "Default")
      (node (ref "JP4") (pin "4") (pinfunction "4_4") (pintype "passive"))
      (node (ref "R34") (pin "1") (pinfunction "1_1") (pintype "passive"))
    )
    (net (code "65") (name "Net-(LED1-PadA)") (class "Default")
      (node (ref "LED1") (pin "A") (pinfunction "A_A") (pintype "passive"))
      (node (ref "R35") (pin "1") (pinfunction "1_1") (pintype "passive"))
    )
    (net (code "66") (name "Net-(LED2-PadA)") (class "Default")
      (node (ref "LED2") (pin "A") (pinfunction "A_A") (pintype "passive"))
      (node (ref "R36") (pin "1") (pinfunction "1_1") (pintype "passive"))
    )
    (net (code "67") (name "Net-(Q1-E)") (class "Default")
      (node (ref "Q1") (pin "3") (pinfunction "E_3") (pintype "passive"))
      (node (ref "R1") (pin "2") (pinfunction "2_2") (pintype "passive"))
    )
    (net (code "68") (name "Net-(Q2-E)") (class "Default")
      (node (ref "Q2") (pin "3") (pinfunction "E_3") (pintype "passive"))
      (node (ref "R15") (pin "2") (pinfunction "2_2") (pintype "passive"))
    )
    (net (code "69") (name "Net-(Q3-E)") (class "Default")
      (node (ref "Q3") (pin "3") (pinfunction "E_3") (pintype "passive"))
      (node (ref "Q4") (pin "3") (pinfunction "E_3") (pintype "passive"))
      (node (ref "R14") (pin "2") (pinfunction "2_2") (pintype "passive"))
    )
    (net (code "70") (name "Net-(R33-A)") (class "Default")
      (node (ref "R17") (pin "1") (pinfunction "1_1") (pintype "passive"))
      (node (ref "R33") (pin "2") (pinfunction "S_2") (pintype "passive"))
      (node (ref "R33") (pin "3") (pinfunction "A_3") (pintype "passive"))
    )
    (net (code "71") (name "Net-(R43-A)") (class "Default")
      (node (ref "R18") (pin "1") (pinfunction "1_1") (pintype "passive"))
      (node (ref "R43") (pin "2") (pinfunction "S_2") (pintype "passive"))
      (node (ref "R43") (pin "3") (pinfunction "A_3") (pintype "passive"))
    )
    (net (code "72") (name "VCC") (class "Default")
      (node (ref "C11") (pin "+") (pinfunction "+_+") (pintype "passive"))
      (node (ref "C13") (pin "1") (pinfunction "1_1") (pintype "passive"))
      (node (ref "C29") (pin "1") (pinfunction "1_1") (pintype "passive"))
      (node (ref "C6") (pin "1") (pinfunction "1_1") (pintype "passive"))
      (node (ref "C8") (pin "1") (pinfunction "1_1") (pintype "passive"))
      (node (ref "C9") (pin "1") (pinfunction "1_1") (pintype "passive"))
      (node (ref "IC1") (pin "4") (pinfunction "V+_4") (pintype "power_in"))
      (node (ref "IC2") (pin "11") (pinfunction "V+_11") (pintype "power_in"))
      (node (ref "IC3") (pin "11") (pinfunction "V+_11") (pintype "power_in"))
      (node (ref "IC4") (pin "11") (pinfunction "V+_11") (pintype "power_in"))
      (node (ref "IC5") (pin "8") (pinfunction "V+_8") (pintype "power_in"))
      (node (ref "IC8") (pin "16") (pinfunction "VCC_16") (pintype "power_in"))
      (node (ref "JP2") (pin "4") (pinfunction "4_4") (pintype "passive"))
      (node (ref "R41") (pin "2") (pinfunction "2_2") (pintype "passive"))
      (node (ref "R42") (pin "2") (pinfunction "2_2") (pintype "passive"))
    )
    (net (code "73") (name "VEE") (class "Default")
      (node (ref "C16") (pin "2") (pinfunction "2_2") (pintype "passive"))
      (node (ref "C18") (pin "2") (pinfunction "2_2") (pintype "passive"))
      (node (ref "C19") (pin "2") (pinfunction "2_2") (pintype "passive"))
      (node (ref "C20") (pin "-") (pinfunction "-_-") (pintype "passive"))
      (node (ref "C3") (pin "2") (pinfunction "2_2") (pintype "passive"))
      (node (ref "C30") (pin "2") (pinfunction "2_2") (pintype "passive"))
      (node (ref "IC1") (pin "11") (pinfunction "V-_11") (pintype "power_in"))
      (node (ref "IC2") (pin "6") (pinfunction "V-_6") (pintype "power_in"))
      (node (ref "IC3") (pin "6") (pinfunction "V-_6") (pintype "power_in"))
      (node (ref "IC4") (pin "6") (pinfunction "V-_6") (pintype "power_in"))
      (node (ref "IC5") (pin "4") (pinfunction "V-_4") (pintype "power_in"))
      (node (ref "IC8") (pin "7") (pinfunction "VEE_7") (pintype "power_in"))
      (node (ref "JP2") (pin "2") (pinfunction "2_2") (pintype "passive"))
      (node (ref "R10") (pin "1") (pinfunction "1_1") (pintype "passive"))
      (node (ref "R24") (pin "1") (pinfunction "1_1") (pintype "passive"))
      (node (ref "R28") (pin "1") (pinfunction "1_1") (pintype "passive"))
      (node (ref "R40") (pin "2") (pinfunction "2_2") (pintype "passive"))
      (node (ref "R6") (pin "1") (pinfunction "1_1") (pintype "passive"))
    )
    (net (code "74") (name "unconnected-(IC2C-I_DIODE-Pad2)") (class "Default")
      (node (ref "IC2") (pin "2") (pinfunction "I_DIODE_2") (pintype "input"))
    )
    (net (code "75") (name "unconnected-(IC2D-I_DIODE-Pad15)") (class "Default")
      (node (ref "IC2") (pin "15") (pinfunction "I_DIODE_15") (pintype "input"))
    )
    (net (code "76") (name "unconnected-(IC3C-I_DIODE-Pad2)") (class "Default")
      (node (ref "IC3") (pin "2") (pinfunction "I_DIODE_2") (pintype "input"))
    )
    (net (code "77") (name "unconnected-(IC3D-I_DIODE-Pad15)") (class "Default")
      (node (ref "IC3") (pin "15") (pinfunction "I_DIODE_15") (pintype "input"))
    )
    (net (code "78") (name "unconnected-(IC4A-B-Pad7)") (class "Default")
      (node (ref "IC4") (pin "7") (pinfunction "B_7") (pintype "passive"))
    )
    (net (code "79") (name "unconnected-(IC4A-E-Pad8)") (class "Default")
      (node (ref "IC4") (pin "8") (pinfunction "E_8") (pintype "passive"))
    )
    (net (code "80") (name "unconnected-(IC4B-B-Pad10)") (class "Default")
      (node (ref "IC4") (pin "10") (pinfunction "B_10") (pintype "passive"))
    )
    (net (code "81") (name "unconnected-(IC4B-E-Pad9)") (class "Default")
      (node (ref "IC4") (pin "9") (pinfunction "E_9") (pintype "passive"))
    )
    (net (code "82") (name "unconnected-(IC4C-I_DIODE-Pad2)") (class "Default")
      (node (ref "IC4") (pin "2") (pinfunction "I_DIODE_2") (pintype "input"))
    )
    (net (code "83") (name "unconnected-(IC4D-I_DIODE-Pad15)") (class "Default")
      (node (ref "IC4") (pin "15") (pinfunction "I_DIODE_15") (pintype "input"))
    )
    (net (code "84") (name "unconnected-(IC7-AREF-Pad21)") (class "Default")
      (node (ref "IC7") (pin "21") (pinfunction "AREF_21") (pintype "passive"))
    )
    (net (code "85") (name "unconnected-(IC7-PB0(ICP)-Pad14)") (class "Default")
      (node (ref "IC7") (pin "14") (pinfunction "PB0(ICP)_14") (pintype "bidirectional"))
    )
    (net (code "86") (name "unconnected-(IC7-PB1(OC1A)-Pad15)") (class "Default")
      (node (ref "IC7") (pin "15") (pinfunction "PB1(OC1A)_15") (pintype "bidirectional"))
    )
    (net (code "87") (name "unconnected-(IC7-PC2(ADC2)-Pad25)") (class "Default")
      (node (ref "IC7") (pin "25") (pinfunction "PC2(ADC2)_25") (pintype "bidirectional"))
    )
    (net (code "88") (name "unconnected-(IC7-PC3(ADC3)-Pad26)") (class "Default")
      (node (ref "IC7") (pin "26") (pinfunction "PC3(ADC3)_26") (pintype "bidirectional"))
    )
    (net (code "89") (name "unconnected-(IC7-PD0(RXD)-Pad2)") (class "Default")
      (node (ref "IC7") (pin "2") (pinfunction "PD0(RXD)_2") (pintype "bidirectional"))
    )
    (net (code "90") (name "unconnected-(IC7-PD3(INT1)-Pad5)") (class "Default")
      (node (ref "IC7") (pin "5") (pinfunction "PD3(INT1)_5") (pintype "bidirectional"))
    )
    (net (code "91") (name "unconnected-(IC7-PD7(AIN1)-Pad13)") (class "Default")
      (node (ref "IC7") (pin "13") (pinfunction "PD7(AIN1)_13") (pintype "bidirectional"))
    )
  )
)
